# nbedmbed_minipro_noimu.net
KiCad netlist of a schematic drawn in EAGLE
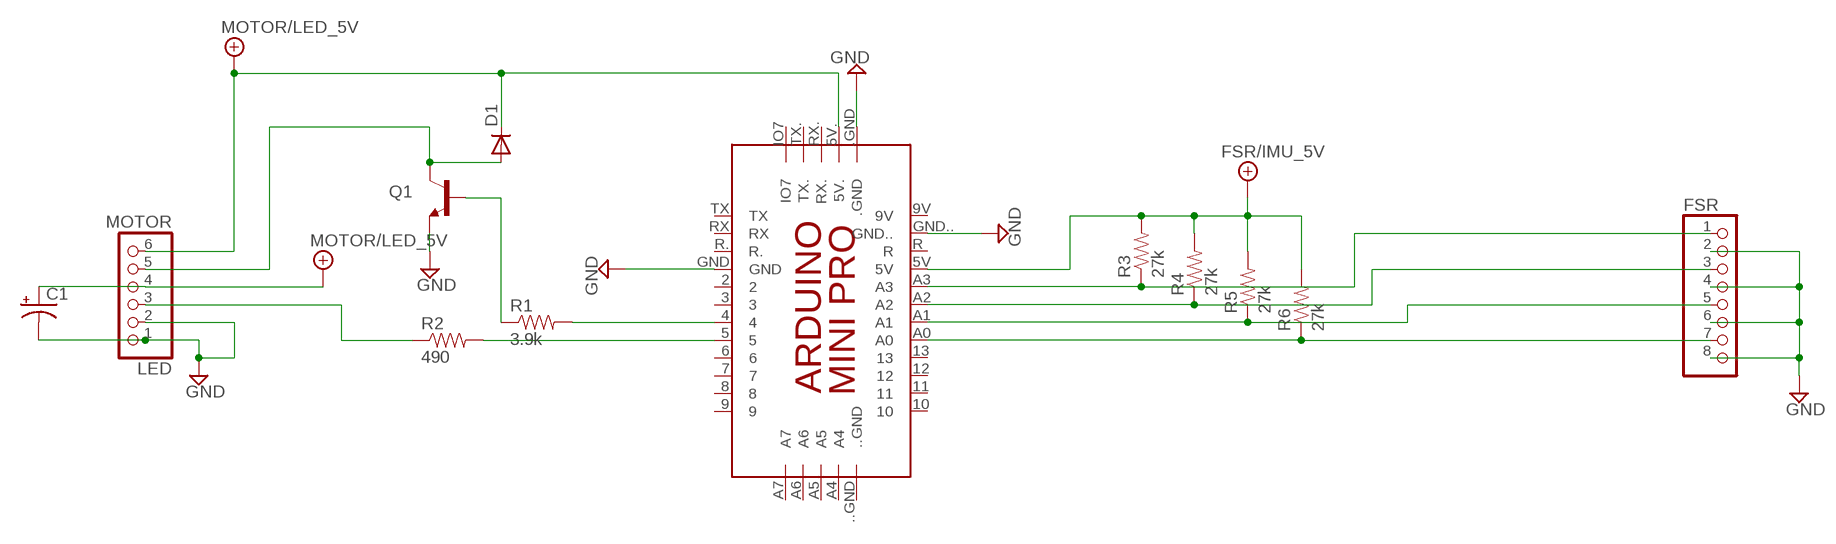
[diagram p0: schematic, sheet 1]

(export (version "E")
  (design (tool "Eeschema 10.0.6"))
  (components
    (comp (ref "C1")
      (value "CAP_POLPTH1")
      (footprint "eagle-import:CPOL-RADIAL-100UF-25V")
      (libsource (lib "eagle-import") (part "CAP_POLPTH1"))
    )
    (comp (ref "D1")
      (value "DIODE1N4148")
      (footprint "eagle-import:DIODE-1N4148")
      (libsource (lib "eagle-import") (part "DIODE1N4148"))
    )
    (comp (ref "FSR")
      (value "PINHD-1X8BIG")
      (footprint "eagle-import:1X08-BIG")
      (libsource (lib "eagle-import") (part "PINHD-1X8BIG"))
    )
    (comp (ref "LED")
      (value "MOTOR")
      (footprint "eagle-import:1X06-BIG")
      (libsource (lib "eagle-import") (part "PINHD-1X6B"))
    )
    (comp (ref "PCB2")
      (value "ARDUINO_MINI_PRO")
      (footprint "eagle-import:ARDUINO_MINI_PRO")
      (libsource (lib "eagle-import") (part "ARDUINO_MINI_PRO"))
    )
    (comp (ref "Q1")
      (value "TRANSISTOR_NPNTO-92-AMMO")
      (footprint "eagle-import:TO-92-AMMO")
      (libsource (lib "eagle-import") (part "TRANSISTOR_NPNTO-92-AMMO"))
    )
    (comp (ref "R1")
      (value "3.9k")
      (footprint "eagle-import:1_6W-RES")
      (libsource (lib "eagle-import") (part "RESISTORPTH-1/6W"))
    )
    (comp (ref "R2")
      (value "490")
      (footprint "eagle-import:1_6W-RES")
      (libsource (lib "eagle-import") (part "RESISTORPTH-1/6W"))
    )
    (comp (ref "R3")
      (value "27k")
      (footprint "eagle-import:1_6W-RES")
      (libsource (lib "eagle-import") (part "RESISTORPTH-1/6W"))
    )
    (comp (ref "R4")
      (value "27k")
      (footprint "eagle-import:1_6W-RES")
      (libsource (lib "eagle-import") (part "RESISTORPTH-1/6W"))
    )
    (comp (ref "R5")
      (value "27k")
      (footprint "eagle-import:1_6W-RES")
      (libsource (lib "eagle-import") (part "RESISTORPTH-1/6W"))
    )
    (comp (ref "R6")
      (value "27k")
      (footprint "eagle-import:1_6W-RES")
      (libsource (lib "eagle-import") (part "RESISTORPTH-1/6W"))
    )
  )
  (nets
    (net (code "1") (name "FSR{slash}IMU_5V") (class "Default")
      (node (ref "PCB2") (pin "5V") (pinfunction "5V_5V") (pintype "bidirectional"))
      (node (ref "R3") (pin "2") (pinfunction "2_2") (pintype "passive"))
      (node (ref "R4") (pin "2") (pinfunction "2_2") (pintype "passive"))
      (node (ref "R5") (pin "2") (pinfunction "2_2") (pintype "passive"))
      (node (ref "R6") (pin "2") (pinfunction "2_2") (pintype "passive"))
    )
    (net (code "2") (name "GND") (class "Default")
      (node (ref "C1") (pin "2") (pinfunction "-_2") (pintype "passive"))
      (node (ref "FSR") (pin "2") (pinfunction "2_2") (pintype "passive"))
      (node (ref "FSR") (pin "4") (pinfunction "4_4") (pintype "passive"))
      (node (ref "FSR") (pin "6") (pinfunction "6_6") (pintype "passive"))
      (node (ref "FSR") (pin "8") (pinfunction "8_8") (pintype "passive"))
      (node (ref "LED") (pin "1") (pinfunction "1_1") (pintype "passive"))
      (node (ref "LED") (pin "2") (pinfunction "2_2") (pintype "passive"))
      (node (ref "PCB2") (pin ".GND") (pinfunction ".GND_.GND") (pintype "bidirectional"))
      (node (ref "PCB2") (pin "GND") (pinfunction "GND_GND") (pintype "bidirectional"))
      (node (ref "PCB2") (pin "GND..") (pinfunction "GND.._GND..") (pintype "bidirectional"))
      (node (ref "Q1") (pin "1") (pinfunction "E_1") (pintype "passive"))
    )
    (net (code "3") (name "MOTOR{slash}LED_5V") (class "Default")
      (node (ref "C1") (pin "1") (pinfunction "+_1") (pintype "passive"))
      (node (ref "D1") (pin "C") (pinfunction "C_C") (pintype "passive"))
      (node (ref "LED") (pin "4") (pinfunction "4_4") (pintype "passive"))
      (node (ref "LED") (pin "6") (pinfunction "6_6") (pintype "passive"))
      (node (ref "PCB2") (pin "5V.") (pinfunction "5V._5V.") (pintype "bidirectional"))
    )
    (net (code "4") (name "Net-(FSR-Pad1)") (class "Default")
      (node (ref "FSR") (pin "1") (pinfunction "1_1") (pintype "passive"))
      (node (ref "PCB2") (pin "A3") (pinfunction "A3_A3") (pintype "bidirectional"))
      (node (ref "R3") (pin "1") (pinfunction "1_1") (pintype "passive"))
    )
    (net (code "5") (name "Net-(FSR-Pad3)") (class "Default")
      (node (ref "FSR") (pin "3") (pinfunction "3_3") (pintype "passive"))
      (node (ref "PCB2") (pin "A2") (pinfunction "A2_A2") (pintype "bidirectional"))
      (node (ref "R4") (pin "1") (pinfunction "1_1") (pintype "passive"))
    )
    (net (code "6") (name "Net-(FSR-Pad5)") (class "Default")
      (node (ref "FSR") (pin "5") (pinfunction "5_5") (pintype "passive"))
      (node (ref "PCB2") (pin "A1") (pinfunction "A1_A1") (pintype "bidirectional"))
      (node (ref "R5") (pin "1") (pinfunction "1_1") (pintype "passive"))
    )
    (net (code "7") (name "Net-(FSR-Pad7)") (class "Default")
      (node (ref "FSR") (pin "7") (pinfunction "7_7") (pintype "passive"))
      (node (ref "PCB2") (pin "A0") (pinfunction "A0_A0") (pintype "bidirectional"))
      (node (ref "R6") (pin "1") (pinfunction "1_1") (pintype "passive"))
    )
    (net (code "8") (name "Net-(LED-Pad3)") (class "Default")
      (node (ref "LED") (pin "3") (pinfunction "3_3") (pintype "passive"))
      (node (ref "R2") (pin "1") (pinfunction "1_1") (pintype "passive"))
    )
    (net (code "9") (name "Net-(PCB2-Pad4)") (class "Default")
      (node (ref "PCB2") (pin "4") (pinfunction "4_4") (pintype "bidirectional"))
      (node (ref "R1") (pin "2") (pinfunction "2_2") (pintype "passive"))
    )
    (net (code "10") (name "Net-(PCB2-Pad5)") (class "Default")
      (node (ref "PCB2") (pin "5") (pinfunction "5_5") (pintype "bidirectional"))
      (node (ref "R2") (pin "2") (pinfunction "2_2") (pintype "passive"))
    )
    (net (code "11") (name "Net-(Q1-B)") (class "Default")
      (node (ref "Q1") (pin "2") (pinfunction "B_2") (pintype "passive"))
      (node (ref "R1") (pin "1") (pinfunction "1_1") (pintype "passive"))
    )
    (net (code "12") (name "Net-(Q1-C)") (class "Default")
      (node (ref "D1") (pin "A") (pinfunction "A_A") (pintype "passive"))
      (node (ref "LED") (pin "5") (pinfunction "5_5") (pintype "passive"))
      (node (ref "Q1") (pin "3") (pinfunction "C_3") (pintype "passive"))
    )
    (net (code "13") (name "unconnected-(PCB2-Pad..GND)") (class "Default")
      (node (ref "PCB2") (pin "..GND") (pinfunction "..GND_..GND") (pintype "bidirectional"))
    )
    (net (code "14") (name "unconnected-(PCB2-Pad2)") (class "Default")
      (node (ref "PCB2") (pin "2") (pinfunction "2_2") (pintype "bidirectional"))
    )
    (net (code "15") (name "unconnected-(PCB2-Pad3)") (class "Default")
      (node (ref "PCB2") (pin "3") (pinfunction "3_3") (pintype "bidirectional"))
    )
    (net (code "16") (name "unconnected-(PCB2-Pad6)") (class "Default")
      (node (ref "PCB2") (pin "6") (pinfunction "6_6") (pintype "bidirectional"))
    )
    (net (code "17") (name "unconnected-(PCB2-Pad7)") (class "Default")
      (node (ref "PCB2") (pin "7") (pinfunction "7_7") (pintype "bidirectional"))
    )
    (net (code "18") (name "unconnected-(PCB2-Pad8)") (class "Default")
      (node (ref "PCB2") (pin "8") (pinfunction "8_8") (pintype "bidirectional"))
    )
    (net (code "19") (name "unconnected-(PCB2-Pad9)") (class "Default")
      (node (ref "PCB2") (pin "9") (pinfunction "9_9") (pintype "bidirectional"))
    )
    (net (code "20") (name "unconnected-(PCB2-Pad9V)") (class "Default")
      (node (ref "PCB2") (pin "9V") (pinfunction "9V_9V") (pintype "bidirectional"))
    )
    (net (code "21") (name "unconnected-(PCB2-Pad10)") (class "Default")
      (node (ref "PCB2") (pin "10") (pinfunction "10_10") (pintype "bidirectional"))
    )
    (net (code "22") (name "unconnected-(PCB2-Pad11)") (class "Default")
      (node (ref "PCB2") (pin "11") (pinfunction "11_11") (pintype "bidirectional"))
    )
    (net (code "23") (name "unconnected-(PCB2-Pad12)") (class "Default")
      (node (ref "PCB2") (pin "12") (pinfunction "12_12") (pintype "bidirectional"))
    )
    (net (code "24") (name "unconnected-(PCB2-Pad13)") (class "Default")
      (node (ref "PCB2") (pin "13") (pinfunction "13_13") (pintype "bidirectional"))
    )
    (net (code "25") (name "unconnected-(PCB2-PadA4)") (class "Default")
      (node (ref "PCB2") (pin "A4") (pinfunction "A4_A4") (pintype "bidirectional"))
    )
    (net (code "26") (name "unconnected-(PCB2-PadA5)") (class "Default")
      (node (ref "PCB2") (pin "A5") (pinfunction "A5_A5") (pintype "bidirectional"))
    )
    (net (code "27") (name "unconnected-(PCB2-PadA6)") (class "Default")
      (node (ref "PCB2") (pin "A6") (pinfunction "A6_A6") (pintype "bidirectional"))
    )
    (net (code "28") (name "unconnected-(PCB2-PadA7)") (class "Default")
      (node (ref "PCB2") (pin "A7") (pinfunction "A7_A7") (pintype "bidirectional"))
    )
    (net (code "29") (name "unconnected-(PCB2-PadIO7)") (class "Default")
      (node (ref "PCB2") (pin "IO7") (pinfunction "IO7_IO7") (pintype "bidirectional"))
    )
    (net (code "30") (name "unconnected-(PCB2-PadR)") (class "Default")
      (node (ref "PCB2") (pin "R") (pinfunction "R_R") (pintype "bidirectional"))
    )
    (net (code "31") (name "unconnected-(PCB2-PadR.)") (class "Default")
      (node (ref "PCB2") (pin "R.") (pinfunction "R._R.") (pintype "bidirectional"))
    )
    (net (code "32") (name "unconnected-(PCB2-PadRX)") (class "Default")
      (node (ref "PCB2") (pin "RX") (pinfunction "RX_RX") (pintype "bidirectional"))
    )
    (net (code "33") (name "unconnected-(PCB2-PadRX.)") (class "Default")
      (node (ref "PCB2") (pin "RX.") (pinfunction "RX._RX.") (pintype "bidirectional"))
    )
    (net (code "34") (name "unconnected-(PCB2-PadTX)") (class "Default")
      (node (ref "PCB2") (pin "TX") (pinfunction "TX_TX") (pintype "bidirectional"))
    )
    (net (code "35") (name "unconnected-(PCB2-PadTX.)") (class "Default")
      (node (ref "PCB2") (pin "TX.") (pinfunction "TX._TX.") (pintype "bidirectional"))
    )
  )
)
